# NCP1200.net
KiCad netlist of a schematic drawn in EAGLE
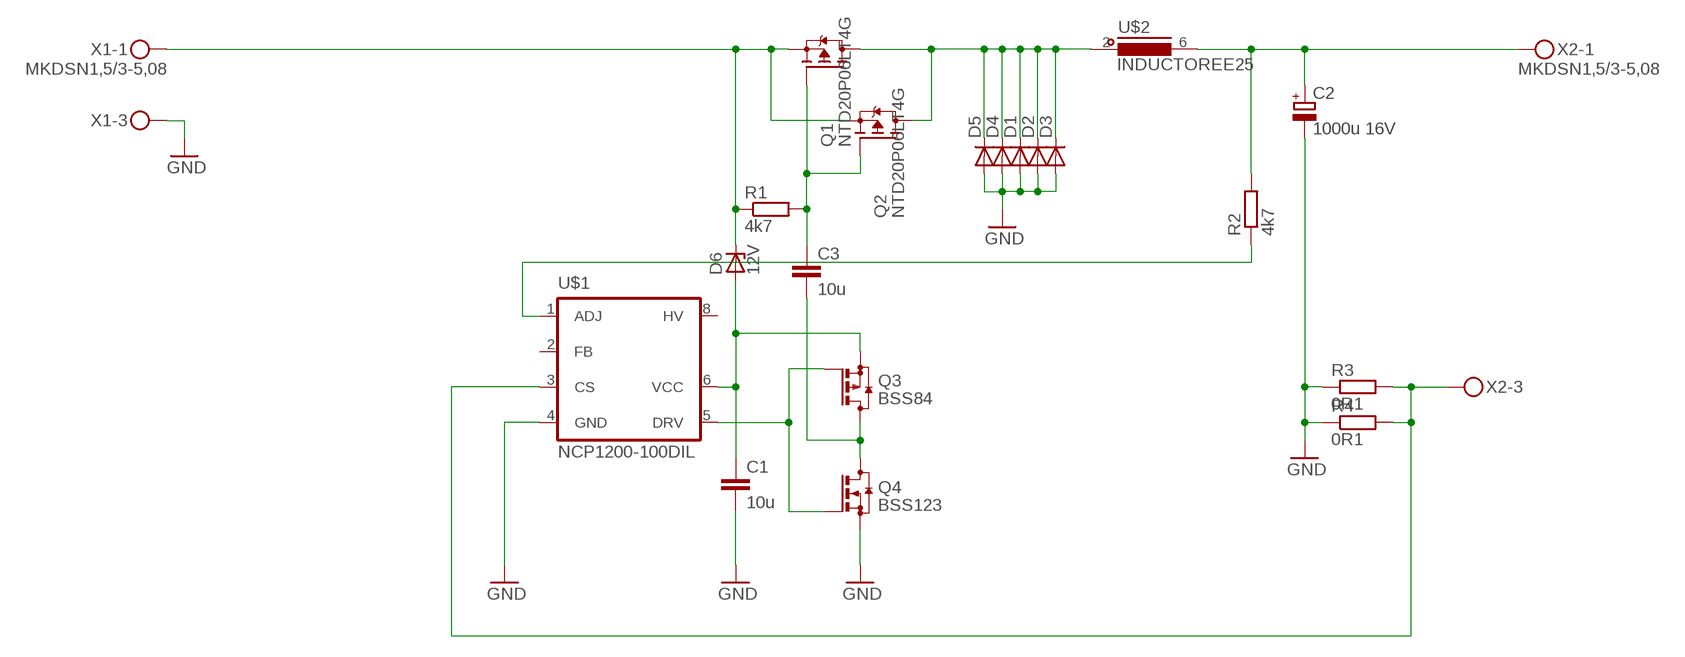
[diagram p0: schematic, sheet 1]

(export (version "E")
  (design (tool "Eeschema 10.0.6"))
  (components
    (comp (ref "C1")
      (value "10u")
      (footprint "eagle-import:C1210")
      (libsource (lib "eagle-import") (part "C-EUC1210"))
    )
    (comp (ref "C2")
      (value "1000u 16V")
      (footprint "eagle-import:E3,5-8")
      (libsource (lib "eagle-import") (part "CPOL-EUE3.5-8"))
    )
    (comp (ref "C3")
      (value "10u")
      (footprint "eagle-import:C1210")
      (libsource (lib "eagle-import") (part "C-EUC1210"))
    )
    (comp (ref "D1")
      (value "DIODE-DO-214AC")
      (footprint "eagle-import:DO-214AC")
      (libsource (lib "eagle-import") (part "DIODE-DO-214AC"))
    )
    (comp (ref "D2")
      (value "DIODE-DO-214AC")
      (footprint "eagle-import:DO-214AC")
      (libsource (lib "eagle-import") (part "DIODE-DO-214AC"))
    )
    (comp (ref "D3")
      (value "DIODE-DO-214AC")
      (footprint "eagle-import:DO-214AC")
      (libsource (lib "eagle-import") (part "DIODE-DO-214AC"))
    )
    (comp (ref "D4")
      (value "DIODE-DO-214AC")
      (footprint "eagle-import:DO-214AC")
      (libsource (lib "eagle-import") (part "DIODE-DO-214AC"))
    )
    (comp (ref "D5")
      (value "DIODE-DO-214AC")
      (footprint "eagle-import:DO-214AC")
      (libsource (lib "eagle-import") (part "DIODE-DO-214AC"))
    )
    (comp (ref "D6")
      (value "12V")
      (footprint "eagle-import:SOD80C")
      (libsource (lib "eagle-import") (part "ZENER-DIODESOD80C"))
    )
    (comp (ref "Q1")
      (value "NTD20P06LT4G")
      (footprint "eagle-import:TO252")
      (libsource (lib "eagle-import") (part "FDD4141TO252"))
    )
    (comp (ref "Q2")
      (value "NTD20P06LT4G")
      (footprint "eagle-import:TO252")
      (libsource (lib "eagle-import") (part "FDD4141TO252"))
    )
    (comp (ref "Q3")
      (value "BSS84")
      (footprint "eagle-import:SOT23")
      (libsource (lib "eagle-import") (part "BSS84"))
    )
    (comp (ref "Q4")
      (value "BSS123")
      (footprint "eagle-import:SOT23")
      (libsource (lib "eagle-import") (part "BSS123"))
    )
    (comp (ref "R1")
      (value "4k7")
      (footprint "eagle-import:R0805")
      (libsource (lib "eagle-import") (part "R-EU_R0805"))
    )
    (comp (ref "R2")
      (value "4k7")
      (footprint "eagle-import:R0805")
      (libsource (lib "eagle-import") (part "R-EU_R0805"))
    )
    (comp (ref "R3")
      (value "0R1")
      (footprint "eagle-import:SQP-10")
      (libsource (lib "eagle-import") (part "R_SQP-10"))
    )
    (comp (ref "R4")
      (value "0R1")
      (footprint "eagle-import:SQP-10")
      (libsource (lib "eagle-import") (part "R_SQP-10"))
    )
    (comp (ref "U$1")
      (value "NCP1200-100DIL")
      (footprint "eagle-import:DIP08")
      (libsource (lib "eagle-import") (part "NCP1200-100DIL"))
    )
    (comp (ref "U$2")
      (value "INDUCTOREE25")
      (footprint "eagle-import:EE25_8PIN_HORIZ")
      (libsource (lib "eagle-import") (part "INDUCTOREE25"))
    )
    (comp (ref "X1")
      (value "MKDSN1,5/3-5,08")
      (footprint "eagle-import:MKDSN1,5_3-5,08")
      (libsource (lib "eagle-import") (part "MKDSN1,5/3-5,08"))
    )
    (comp (ref "X2")
      (value "MKDSN1,5/3-5,08")
      (footprint "eagle-import:MKDSN1,5_3-5,08")
      (libsource (lib "eagle-import") (part "MKDSN1,5/3-5,08"))
    )
  )
  (nets
    (net (code "1") (name "GND") (class "Default")
      (node (ref "C1") (pin "2") (pinfunction "2_2") (pintype "passive"))
      (node (ref "C2") (pin "-") (pinfunction "-_-") (pintype "passive"))
      (node (ref "D1") (pin "A") (pinfunction "A_A") (pintype "passive"))
      (node (ref "D2") (pin "A") (pinfunction "A_A") (pintype "passive"))
      (node (ref "D3") (pin "A") (pinfunction "A_A") (pintype "passive"))
      (node (ref "D4") (pin "A") (pinfunction "A_A") (pintype "passive"))
      (node (ref "D5") (pin "A") (pinfunction "A_A") (pintype "passive"))
      (node (ref "Q4") (pin "2") (pinfunction "S_2") (pintype "passive"))
      (node (ref "R3") (pin "P$1") (pinfunction "1_P$1") (pintype "passive"))
      (node (ref "R4") (pin "P$1") (pinfunction "1_P$1") (pintype "passive"))
      (node (ref "U$1") (pin "4") (pinfunction "GND_4") (pintype "passive"))
      (node (ref "X1") (pin "3") (pinfunction "KL_3") (pintype "passive"))
    )
    (net (code "2") (name "Net-(Q1-D)") (class "Default")
      (node (ref "D1") (pin "C") (pinfunction "C_C") (pintype "passive"))
      (node (ref "D2") (pin "C") (pinfunction "C_C") (pintype "passive"))
      (node (ref "D3") (pin "C") (pinfunction "C_C") (pintype "passive"))
      (node (ref "D4") (pin "C") (pinfunction "C_C") (pintype "passive"))
      (node (ref "D5") (pin "C") (pinfunction "C_C") (pintype "passive"))
      (node (ref "Q1") (pin "3") (pinfunction "D_3") (pintype "passive"))
      (node (ref "Q2") (pin "3") (pinfunction "D_3") (pintype "passive"))
      (node (ref "U$2") (pin "2") (pinfunction "1_2") (pintype "passive"))
    )
    (net (code "3") (name "Net-(Q1-G)") (class "Default")
      (node (ref "C3") (pin "1") (pinfunction "1_1") (pintype "passive"))
      (node (ref "Q1") (pin "1") (pinfunction "G_1") (pintype "passive"))
      (node (ref "Q2") (pin "1") (pinfunction "G_1") (pintype "passive"))
      (node (ref "R1") (pin "2") (pinfunction "2_2") (pintype "passive"))
    )
    (net (code "4") (name "Net-(Q1-S)") (class "Default")
      (node (ref "D6") (pin "C") (pinfunction "C_C") (pintype "passive"))
      (node (ref "Q1") (pin "2") (pinfunction "S_2") (pintype "passive"))
      (node (ref "Q2") (pin "2") (pinfunction "S_2") (pintype "passive"))
      (node (ref "R1") (pin "1") (pinfunction "1_1") (pintype "passive"))
      (node (ref "X1") (pin "1") (pinfunction "KL_1") (pintype "passive"))
    )
    (net (code "5") (name "Net-(Q3-D)") (class "Default")
      (node (ref "C3") (pin "2") (pinfunction "2_2") (pintype "passive"))
      (node (ref "Q3") (pin "3") (pinfunction "D_3") (pintype "passive"))
      (node (ref "Q4") (pin "3") (pinfunction "D_3") (pintype "passive"))
    )
    (net (code "6") (name "Net-(Q3-G)") (class "Default")
      (node (ref "Q3") (pin "1") (pinfunction "G_1") (pintype "passive"))
      (node (ref "Q4") (pin "1") (pinfunction "G_1") (pintype "passive"))
      (node (ref "U$1") (pin "5") (pinfunction "DRV_5") (pintype "power_in"))
    )
    (net (code "7") (name "Net-(Q3-S)") (class "Default")
      (node (ref "C1") (pin "1") (pinfunction "1_1") (pintype "passive"))
      (node (ref "D6") (pin "A") (pinfunction "A_A") (pintype "passive"))
      (node (ref "Q3") (pin "2") (pinfunction "S_2") (pintype "passive"))
      (node (ref "U$1") (pin "6") (pinfunction "VCC_6") (pintype "output"))
    )
    (net (code "8") (name "Net-(R3-2)") (class "Default")
      (node (ref "R3") (pin "P$2") (pinfunction "2_P$2") (pintype "passive"))
      (node (ref "R4") (pin "P$2") (pinfunction "2_P$2") (pintype "passive"))
      (node (ref "U$1") (pin "3") (pinfunction "CS_3") (pintype "input"))
      (node (ref "X2") (pin "3") (pinfunction "KL_3") (pintype "passive"))
    )
    (net (code "9") (name "Net-(U$1-ADJ)") (class "Default")
      (node (ref "R2") (pin "1") (pinfunction "1_1") (pintype "passive"))
      (node (ref "U$1") (pin "1") (pinfunction "ADJ_1") (pintype "passive"))
    )
    (net (code "10") (name "Net-(U$2-2)") (class "Default")
      (node (ref "C2") (pin "+") (pinfunction "+_+") (pintype "passive"))
      (node (ref "R2") (pin "2") (pinfunction "2_2") (pintype "passive"))
      (node (ref "U$2") (pin "6") (pinfunction "2_6") (pintype "passive"))
      (node (ref "X2") (pin "1") (pinfunction "KL_1") (pintype "passive"))
    )
    (net (code "11") (name "unconnected-(U$1-FB-Pad2)") (class "Default")
      (node (ref "U$1") (pin "2") (pinfunction "FB_2") (pintype "input"))
    )
    (net (code "12") (name "unconnected-(U$1-HV-Pad8)") (class "Default")
      (node (ref "U$1") (pin "8") (pinfunction "HV_8") (pintype "passive"))
    )
  )
)
